# StandalonePRG.net
KiCad netlist of a schematic drawn in EAGLE
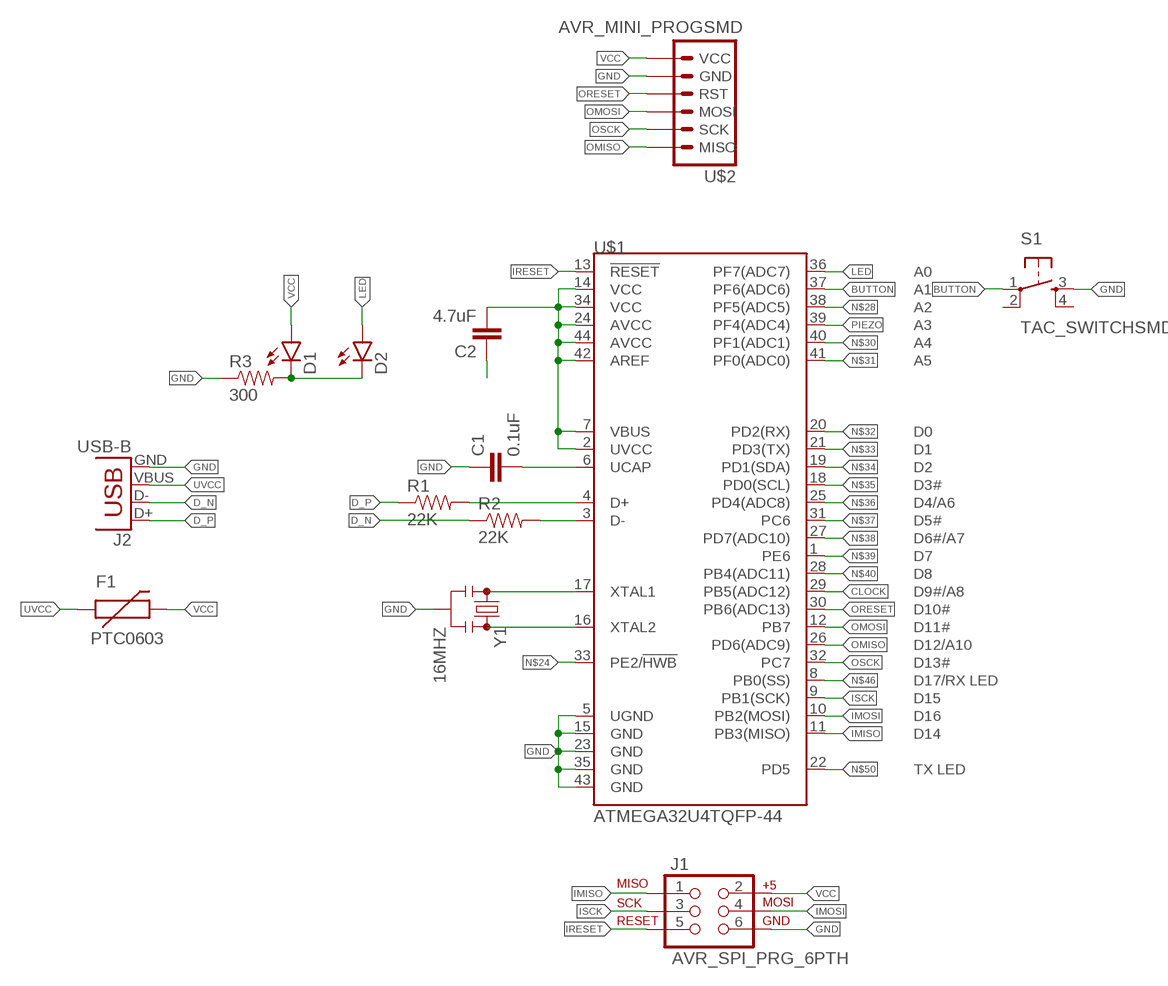
[diagram p0: schematic, sheet 1]

(export (version "E")
  (design (tool "Eeschema 10.0.6"))
  (components
    (comp (ref "C1")
      (value "0.1uF")
      (footprint "eagle-import:0603-CAP")
      (libsource (lib "eagle-import") (part "0.1UF-100V-10%(0603)"))
    )
    (comp (ref "C2")
      (value "4.7uF")
      (footprint "eagle-import:0603-CAP")
      (libsource (lib "eagle-import") (part "4.7UF-6.3V-10%(0603)0603"))
    )
    (comp (ref "D1")
      (value "LED0603")
      (footprint "eagle-import:LED-0603")
      (libsource (lib "eagle-import") (part "LED0603"))
    )
    (comp (ref "D2")
      (value "LED0603")
      (footprint "eagle-import:LED-0603")
      (libsource (lib "eagle-import") (part "LED0603"))
    )
    (comp (ref "F1")
      (value "PTC0603")
      (footprint "eagle-import:0603")
      (libsource (lib "eagle-import") (part "PTC0603"))
    )
    (comp (ref "J1")
      (value "AVR_SPI_PRG_6PTH")
      (footprint "eagle-import:2X3")
      (libsource (lib "eagle-import") (part "AVR_SPI_PRG_6PTH"))
    )
    (comp (ref "J2")
      (value "USB-B")
      (footprint "eagle-import:USB-B-PTH")
      (libsource (lib "eagle-import") (part "USBPTH"))
    )
    (comp (ref "R1")
      (value "22K")
      (footprint "eagle-import:0603-RES")
      (libsource (lib "eagle-import") (part "22KOHM1/10W1%(0603)"))
    )
    (comp (ref "R2")
      (value "22K")
      (footprint "eagle-import:0603-RES")
      (libsource (lib "eagle-import") (part "22KOHM1/10W1%(0603)"))
    )
    (comp (ref "R3")
      (value "300")
      (footprint "eagle-import:0603-RES")
      (libsource (lib "eagle-import") (part "300OHM-1/10W-1%(0603)"))
    )
    (comp (ref "S1")
      (value "TAC_SWITCHSMD")
      (footprint "eagle-import:TACTILE-SWITCH-SMD")
      (libsource (lib "eagle-import") (part "TAC_SWITCHSMD"))
    )
    (comp (ref "U$1")
      (value "ATMEGA32U4TQFP-44")
      (footprint "eagle-import:TQFP44")
      (libsource (lib "eagle-import") (part "ATMEGA32U4TQFP-44"))
    )
    (comp (ref "U$2")
      (value "AVR_MINI_PROGSMD")
      (footprint "eagle-import:AVR_MINI_PROG")
      (libsource (lib "eagle-import") (part "AVR_MINI_PROGSMD"))
    )
    (comp (ref "Y1")
      (value "16MHZ")
      (footprint "eagle-import:RESONATOR-SMD")
      (libsource (lib "eagle-import") (part "RESONATOR16MHZ"))
    )
  )
  (nets
    (net (code "1") (name "BUTTON") (class "Default")
      (node (ref "S1") (pin "1") (pinfunction "1_1") (pintype "passive"))
      (node (ref "U$1") (pin "37") (pinfunction "PF6(ADC6)_37") (pintype "bidirectional"))
    )
    (net (code "2") (name "CLOCK") (class "Default")
      (node (ref "U$1") (pin "29") (pinfunction "PB5(ADC12)_29") (pintype "bidirectional"))
    )
    (net (code "3") (name "D_N") (class "Default")
      (node (ref "J2") (pin "D-") (pinfunction "D-_D-") (pintype "bidirectional"))
      (node (ref "R2") (pin "1") (pinfunction "1_1") (pintype "passive"))
    )
    (net (code "4") (name "D_P") (class "Default")
      (node (ref "J2") (pin "D+") (pinfunction "D+_D+") (pintype "bidirectional"))
      (node (ref "R1") (pin "1") (pinfunction "1_1") (pintype "passive"))
    )
    (net (code "5") (name "GND") (class "Default")
      (node (ref "C1") (pin "1") (pinfunction "1_1") (pintype "passive"))
      (node (ref "C2") (pin "1") (pinfunction "1_1") (pintype "passive"))
      (node (ref "J1") (pin "6") (pinfunction "6_6") (pintype "passive"))
      (node (ref "J2") (pin "GND") (pinfunction "GND_GND") (pintype "bidirectional"))
      (node (ref "R3") (pin "1") (pinfunction "1_1") (pintype "passive"))
      (node (ref "S1") (pin "3") (pinfunction "3_3") (pintype "passive"))
      (node (ref "U$1") (pin "15") (pinfunction "GND_15") (pintype "bidirectional"))
      (node (ref "U$1") (pin "23") (pinfunction "GND_23") (pintype "bidirectional"))
      (node (ref "U$1") (pin "35") (pinfunction "GND_35") (pintype "bidirectional"))
      (node (ref "U$1") (pin "43") (pinfunction "GND_43") (pintype "bidirectional"))
      (node (ref "U$1") (pin "5") (pinfunction "UGND_5") (pintype "bidirectional"))
      (node (ref "U$2") (pin "2") (pinfunction "GND_2") (pintype "passive"))
      (node (ref "Y1") (pin "2") (pinfunction "2_2") (pintype "passive"))
    )
    (net (code "6") (name "IMISO") (class "Default")
      (node (ref "J1") (pin "1") (pinfunction "1_1") (pintype "passive"))
      (node (ref "U$1") (pin "11") (pinfunction "PB3(MISO)_11") (pintype "bidirectional"))
    )
    (net (code "7") (name "IMOSI") (class "Default")
      (node (ref "J1") (pin "4") (pinfunction "4_4") (pintype "passive"))
      (node (ref "U$1") (pin "10") (pinfunction "PB2(MOSI)_10") (pintype "bidirectional"))
    )
    (net (code "8") (name "IRESET") (class "Default")
      (node (ref "J1") (pin "5") (pinfunction "5_5") (pintype "passive"))
      (node (ref "U$1") (pin "13") (pinfunction "~{RESET}_13") (pintype "bidirectional"))
    )
    (net (code "9") (name "ISCK") (class "Default")
      (node (ref "J1") (pin "3") (pinfunction "3_3") (pintype "passive"))
      (node (ref "U$1") (pin "9") (pinfunction "PB1(SCK)_9") (pintype "bidirectional"))
    )
    (net (code "10") (name "LED") (class "Default")
      (node (ref "D2") (pin "A") (pinfunction "A_A") (pintype "passive"))
      (node (ref "U$1") (pin "36") (pinfunction "PF7(ADC7)_36") (pintype "bidirectional"))
    )
    (net (code "11") (name "N$24") (class "Default")
      (node (ref "U$1") (pin "33") (pinfunction "PE2/~{HWB}_33") (pintype "bidirectional"))
    )
    (net (code "12") (name "N$28") (class "Default")
      (node (ref "U$1") (pin "38") (pinfunction "PF5(ADC5)_38") (pintype "bidirectional"))
    )
    (net (code "13") (name "N$30") (class "Default")
      (node (ref "U$1") (pin "40") (pinfunction "PF1(ADC1)_40") (pintype "bidirectional"))
    )
    (net (code "14") (name "N$31") (class "Default")
      (node (ref "U$1") (pin "41") (pinfunction "PF0(ADC0)_41") (pintype "bidirectional"))
    )
    (net (code "15") (name "N$32") (class "Default")
      (node (ref "U$1") (pin "20") (pinfunction "PD2(RX)_20") (pintype "bidirectional"))
    )
    (net (code "16") (name "N$33") (class "Default")
      (node (ref "U$1") (pin "21") (pinfunction "PD3(TX)_21") (pintype "bidirectional"))
    )
    (net (code "17") (name "N$34") (class "Default")
      (node (ref "U$1") (pin "19") (pinfunction "PD1(SDA)_19") (pintype "bidirectional"))
    )
    (net (code "18") (name "N$35") (class "Default")
      (node (ref "U$1") (pin "18") (pinfunction "PD0(SCL)_18") (pintype "bidirectional"))
    )
    (net (code "19") (name "N$36") (class "Default")
      (node (ref "U$1") (pin "25") (pinfunction "PD4(ADC8)_25") (pintype "bidirectional"))
    )
    (net (code "20") (name "N$37") (class "Default")
      (node (ref "U$1") (pin "31") (pinfunction "PC6_31") (pintype "bidirectional"))
    )
    (net (code "21") (name "N$38") (class "Default")
      (node (ref "U$1") (pin "27") (pinfunction "PD7(ADC10)_27") (pintype "bidirectional"))
    )
    (net (code "22") (name "N$39") (class "Default")
      (node (ref "U$1") (pin "1") (pinfunction "PE6_1") (pintype "bidirectional"))
    )
    (net (code "23") (name "N$40") (class "Default")
      (node (ref "U$1") (pin "28") (pinfunction "PB4(ADC11)_28") (pintype "bidirectional"))
    )
    (net (code "24") (name "N$46") (class "Default")
      (node (ref "U$1") (pin "8") (pinfunction "PB0(SS)_8") (pintype "bidirectional"))
    )
    (net (code "25") (name "N$50") (class "Default")
      (node (ref "U$1") (pin "22") (pinfunction "PD5_22") (pintype "bidirectional"))
    )
    (net (code "26") (name "Net-(D1-PadC)") (class "Default")
      (node (ref "D1") (pin "C") (pinfunction "C_C") (pintype "passive"))
      (node (ref "D2") (pin "C") (pinfunction "C_C") (pintype "passive"))
      (node (ref "R3") (pin "2") (pinfunction "2_2") (pintype "passive"))
    )
    (net (code "27") (name "Net-(U$1-D+)") (class "Default")
      (node (ref "R1") (pin "2") (pinfunction "2_2") (pintype "passive"))
      (node (ref "U$1") (pin "4") (pinfunction "D+_4") (pintype "bidirectional"))
    )
    (net (code "28") (name "Net-(U$1-D-)") (class "Default")
      (node (ref "R2") (pin "2") (pinfunction "2_2") (pintype "passive"))
      (node (ref "U$1") (pin "3") (pinfunction "D-_3") (pintype "bidirectional"))
    )
    (net (code "29") (name "Net-(U$1-UCAP)") (class "Default")
      (node (ref "C1") (pin "2") (pinfunction "2_2") (pintype "passive"))
      (node (ref "U$1") (pin "6") (pinfunction "UCAP_6") (pintype "bidirectional"))
    )
    (net (code "30") (name "Net-(U$1-XTAL1)") (class "Default")
      (node (ref "U$1") (pin "17") (pinfunction "XTAL1_17") (pintype "bidirectional"))
      (node (ref "Y1") (pin "1") (pinfunction "1_1") (pintype "passive"))
    )
    (net (code "31") (name "Net-(U$1-XTAL2)") (class "Default")
      (node (ref "U$1") (pin "16") (pinfunction "XTAL2_16") (pintype "bidirectional"))
      (node (ref "Y1") (pin "3") (pinfunction "3_3") (pintype "passive"))
    )
    (net (code "32") (name "OMISO") (class "Default")
      (node (ref "U$1") (pin "26") (pinfunction "PD6(ADC9)_26") (pintype "bidirectional"))
      (node (ref "U$2") (pin "6") (pinfunction "MISO_6") (pintype "passive"))
    )
    (net (code "33") (name "OMOSI") (class "Default")
      (node (ref "U$1") (pin "12") (pinfunction "PB7_12") (pintype "bidirectional"))
      (node (ref "U$2") (pin "4") (pinfunction "MOSI_4") (pintype "passive"))
    )
    (net (code "34") (name "ORESET") (class "Default")
      (node (ref "U$1") (pin "30") (pinfunction "PB6(ADC13)_30") (pintype "bidirectional"))
      (node (ref "U$2") (pin "3") (pinfunction "RST_3") (pintype "passive"))
    )
    (net (code "35") (name "OSCK") (class "Default")
      (node (ref "U$1") (pin "32") (pinfunction "PC7_32") (pintype "bidirectional"))
      (node (ref "U$2") (pin "5") (pinfunction "SCK_5") (pintype "passive"))
    )
    (net (code "36") (name "PIEZO") (class "Default")
      (node (ref "U$1") (pin "39") (pinfunction "PF4(ADC4)_39") (pintype "bidirectional"))
    )
    (net (code "37") (name "UVCC") (class "Default")
      (node (ref "F1") (pin "1") (pinfunction "1_1") (pintype "bidirectional"))
      (node (ref "J2") (pin "VBUS") (pinfunction "VBUS_VBUS") (pintype "bidirectional"))
    )
    (net (code "38") (name "VCC") (class "Default")
      (node (ref "C2") (pin "2") (pinfunction "2_2") (pintype "passive"))
      (node (ref "D1") (pin "A") (pinfunction "A_A") (pintype "passive"))
      (node (ref "F1") (pin "2") (pinfunction "2_2") (pintype "bidirectional"))
      (node (ref "J1") (pin "2") (pinfunction "2_2") (pintype "passive"))
      (node (ref "U$1") (pin "14") (pinfunction "VCC_14") (pintype "bidirectional"))
      (node (ref "U$1") (pin "2") (pinfunction "UVCC_2") (pintype "bidirectional"))
      (node (ref "U$1") (pin "24") (pinfunction "AVCC_24") (pintype "bidirectional"))
      (node (ref "U$1") (pin "34") (pinfunction "VCC_34") (pintype "bidirectional"))
      (node (ref "U$1") (pin "42") (pinfunction "AREF_42") (pintype "bidirectional"))
      (node (ref "U$1") (pin "44") (pinfunction "AVCC_44") (pintype "bidirectional"))
      (node (ref "U$1") (pin "7") (pinfunction "VBUS_7") (pintype "bidirectional"))
      (node (ref "U$2") (pin "1") (pinfunction "VCC_1") (pintype "passive"))
    )
    (net (code "39") (name "unconnected-(S1-Pad2)") (class "Default")
      (node (ref "S1") (pin "2") (pinfunction "2_2") (pintype "passive"))
    )
    (net (code "40") (name "unconnected-(S1-Pad4)") (class "Default")
      (node (ref "S1") (pin "4") (pinfunction "4_4") (pintype "passive"))
    )
  )
)
